# Lighting_Schematic_Design.net
KiCad netlist of a schematic drawn in EAGLE
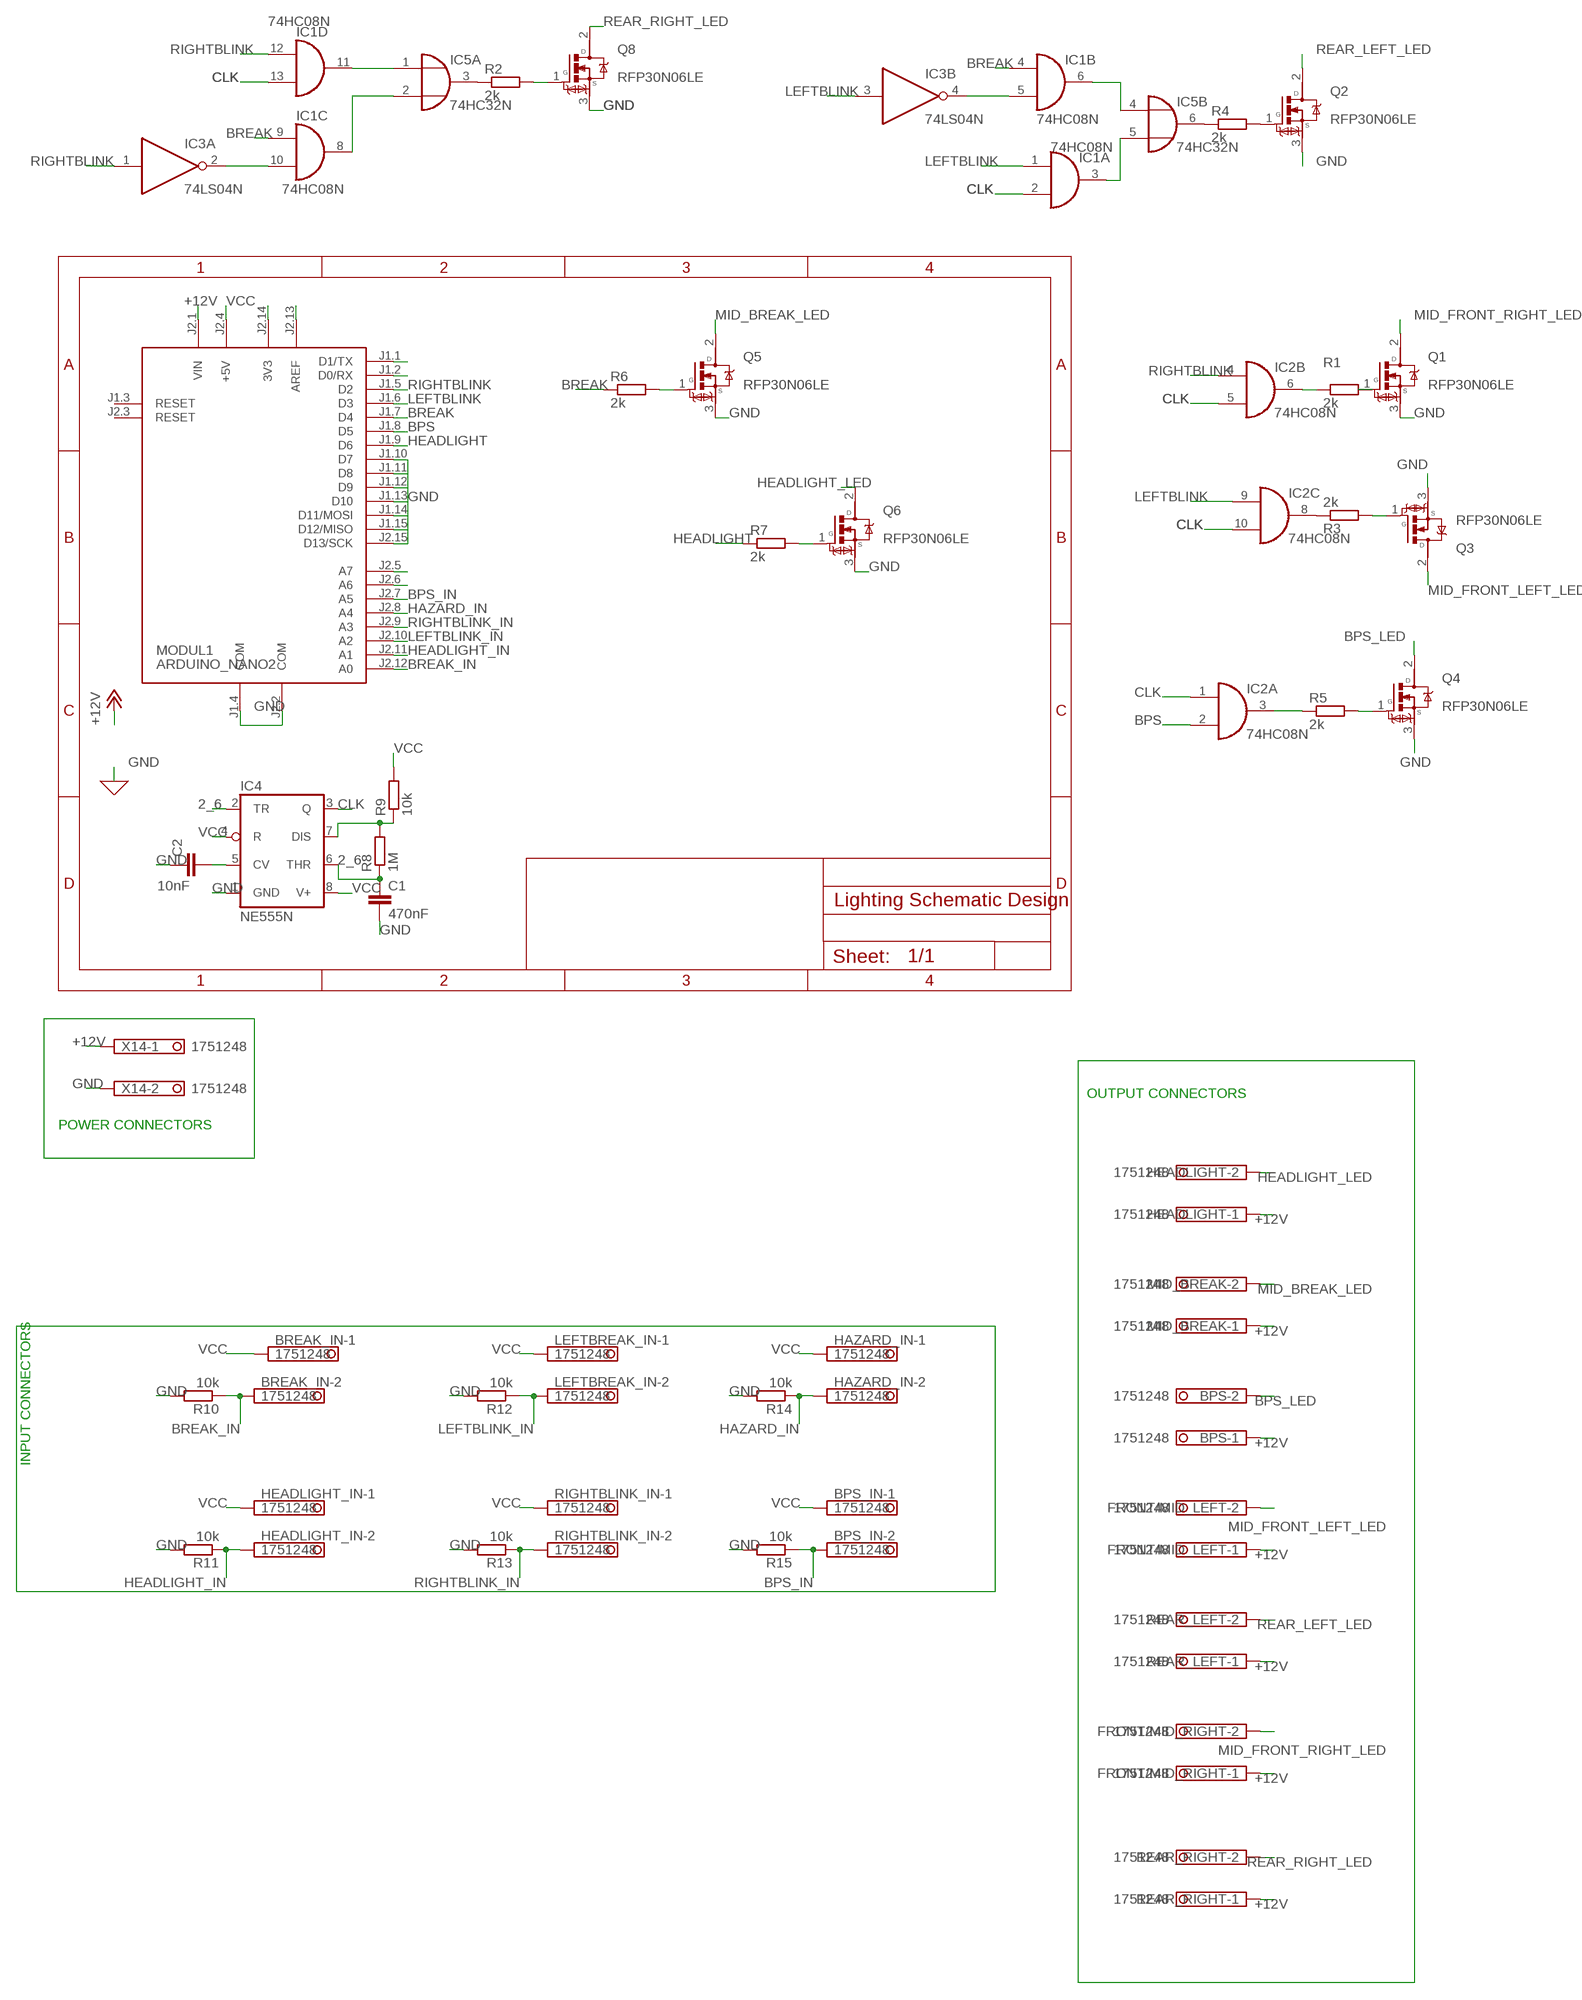
[diagram p0: schematic, sheet 1]

(export (version "E")
  (design (tool "Eeschema 10.0.6"))
  (components
    (comp (ref "BPS")
      (value "1751248")
      (footprint "eagle-import:1751248")
      (libsource (lib "eagle-import") (part "1751248"))
    )
    (comp (ref "BPS_IN")
      (value "1751248")
      (footprint "eagle-import:1751248")
      (libsource (lib "eagle-import") (part "1751248"))
    )
    (comp (ref "BREAK_IN")
      (value "1751248")
      (footprint "eagle-import:1751248")
      (libsource (lib "eagle-import") (part "1751248"))
    )
    (comp (ref "C1")
      (value "470nF")
      (footprint "eagle-import:C2.5-2")
      (libsource (lib "eagle-import") (part "C2.5/2"))
    )
    (comp (ref "C2")
      (value "10nF")
      (footprint "eagle-import:C2.5-2")
      (libsource (lib "eagle-import") (part "C2.5/2"))
    )
    (comp (ref "FRONT/MID_LEFT")
      (value "1751248")
      (footprint "eagle-import:1751248")
      (libsource (lib "eagle-import") (part "1751248"))
    )
    (comp (ref "FRONT/MID_RIGHT")
      (value "1751248")
      (footprint "eagle-import:1751248")
      (libsource (lib "eagle-import") (part "1751248"))
    )
    (comp (ref "HAZARD_IN")
      (value "1751248")
      (footprint "eagle-import:1751248")
      (libsource (lib "eagle-import") (part "1751248"))
    )
    (comp (ref "HEADLIGHT")
      (value "1751248")
      (footprint "eagle-import:1751248")
      (libsource (lib "eagle-import") (part "1751248"))
    )
    (comp (ref "HEADLIGHT_IN")
      (value "1751248")
      (footprint "eagle-import:1751248")
      (libsource (lib "eagle-import") (part "1751248"))
    )
    (comp (ref "IC1")
      (value "74HC08N")
      (footprint "eagle-import:DIL14")
      (libsource (lib "eagle-import") (part "7408NHC"))
    )
    (comp (ref "IC2")
      (value "74HC08N")
      (footprint "eagle-import:DIL14")
      (libsource (lib "eagle-import") (part "7408NHC"))
    )
    (comp (ref "IC3")
      (value "74LS04N")
      (footprint "eagle-import:DIL14")
      (libsource (lib "eagle-import") (part "7404NLS"))
    )
    (comp (ref "IC4")
      (value "NE555N")
      (footprint "eagle-import:DIL08")
      (libsource (lib "eagle-import") (part "555NNE"))
    )
    (comp (ref "IC5")
      (value "74HC32N")
      (footprint "eagle-import:DIL14")
      (libsource (lib "eagle-import") (part "7432NHC"))
    )
    (comp (ref "LEFTBREAK_IN")
      (value "1751248")
      (footprint "eagle-import:1751248")
      (libsource (lib "eagle-import") (part "1751248"))
    )
    (comp (ref "MID_BREAK")
      (value "1751248")
      (footprint "eagle-import:1751248")
      (libsource (lib "eagle-import") (part "1751248"))
    )
    (comp (ref "MODUL1")
      (value "ARDUINO_NANO2")
      (footprint "eagle-import:ARDUINO_NANO2")
      (libsource (lib "eagle-import") (part "ARDUINO_NANO2"))
    )
    (comp (ref "Q1")
      (value "RFP30N06LE")
      (footprint "eagle-import:TRANS_RFP30N06LE")
      (fields (field (name "MF") "ON Semiconductor"))
      (libsource (lib "eagle-import") (part "RFP30N06LE"))
    )
    (comp (ref "Q2")
      (value "RFP30N06LE")
      (footprint "eagle-import:TRANS_RFP30N06LE")
      (fields (field (name "MF") "ON Semiconductor"))
      (libsource (lib "eagle-import") (part "RFP30N06LE"))
    )
    (comp (ref "Q3")
      (value "RFP30N06LE")
      (footprint "eagle-import:TRANS_RFP30N06LE")
      (fields (field (name "MF") "ON Semiconductor"))
      (libsource (lib "eagle-import") (part "RFP30N06LE"))
    )
    (comp (ref "Q4")
      (value "RFP30N06LE")
      (footprint "eagle-import:TRANS_RFP30N06LE")
      (fields (field (name "MF") "ON Semiconductor"))
      (libsource (lib "eagle-import") (part "RFP30N06LE"))
    )
    (comp (ref "Q5")
      (value "RFP30N06LE")
      (footprint "eagle-import:TRANS_RFP30N06LE")
      (fields (field (name "MF") "ON Semiconductor"))
      (libsource (lib "eagle-import") (part "RFP30N06LE"))
    )
    (comp (ref "Q6")
      (value "RFP30N06LE")
      (footprint "eagle-import:TRANS_RFP30N06LE")
      (fields (field (name "MF") "ON Semiconductor"))
      (libsource (lib "eagle-import") (part "RFP30N06LE"))
    )
    (comp (ref "Q8")
      (value "RFP30N06LE")
      (footprint "eagle-import:TRANS_RFP30N06LE")
      (fields (field (name "MF") "ON Semiconductor"))
      (libsource (lib "eagle-import") (part "RFP30N06LE"))
    )
    (comp (ref "R1")
      (value "2k")
      (footprint "eagle-import:0204_5")
      (libsource (lib "eagle-import") (part "R-EU_0204/5"))
    )
    (comp (ref "R2")
      (value "2k")
      (footprint "eagle-import:0204_5")
      (libsource (lib "eagle-import") (part "R-EU_0204/5"))
    )
    (comp (ref "R3")
      (value "2k")
      (footprint "eagle-import:0204_5")
      (libsource (lib "eagle-import") (part "R-EU_0204/5"))
    )
    (comp (ref "R4")
      (value "2k")
      (footprint "eagle-import:0204_5")
      (libsource (lib "eagle-import") (part "R-EU_0204/5"))
    )
    (comp (ref "R5")
      (value "2k")
      (footprint "eagle-import:0204_5")
      (libsource (lib "eagle-import") (part "R-EU_0204/5"))
    )
    (comp (ref "R6")
      (value "2k")
      (footprint "eagle-import:0204_5")
      (libsource (lib "eagle-import") (part "R-EU_0204/5"))
    )
    (comp (ref "R7")
      (value "2k")
      (footprint "eagle-import:0204_5")
      (libsource (lib "eagle-import") (part "R-EU_0204/5"))
    )
    (comp (ref "R8")
      (value "1M")
      (footprint "eagle-import:0204_5")
      (libsource (lib "eagle-import") (part "R-EU_0204/5"))
    )
    (comp (ref "R9")
      (value "10k")
      (footprint "eagle-import:0204_5")
      (libsource (lib "eagle-import") (part "R-EU_0204/5"))
    )
    (comp (ref "R10")
      (value "10k")
      (footprint "eagle-import:0204_5")
      (libsource (lib "eagle-import") (part "R-EU_0204/5"))
    )
    (comp (ref "R11")
      (value "10k")
      (footprint "eagle-import:0204_5")
      (libsource (lib "eagle-import") (part "R-EU_0204/5"))
    )
    (comp (ref "R12")
      (value "10k")
      (footprint "eagle-import:0204_5")
      (libsource (lib "eagle-import") (part "R-EU_0204/5"))
    )
    (comp (ref "R13")
      (value "10k")
      (footprint "eagle-import:0204_5")
      (libsource (lib "eagle-import") (part "R-EU_0204/5"))
    )
    (comp (ref "R14")
      (value "10k")
      (footprint "eagle-import:0204_5")
      (libsource (lib "eagle-import") (part "R-EU_0204/5"))
    )
    (comp (ref "R15")
      (value "10k")
      (footprint "eagle-import:0204_5")
      (libsource (lib "eagle-import") (part "R-EU_0204/5"))
    )
    (comp (ref "REAR_LEFT")
      (value "1751248")
      (footprint "eagle-import:1751248")
      (libsource (lib "eagle-import") (part "1751248"))
    )
    (comp (ref "REAR_RIGHT")
      (value "1751248")
      (footprint "eagle-import:1751248")
      (libsource (lib "eagle-import") (part "1751248"))
    )
    (comp (ref "RIGHTBLINK_IN")
      (value "1751248")
      (footprint "eagle-import:1751248")
      (libsource (lib "eagle-import") (part "1751248"))
    )
    (comp (ref "X14")
      (value "1751248")
      (footprint "eagle-import:1751248")
      (libsource (lib "eagle-import") (part "1751248"))
    )
  )
  (nets
    (net (code "1") (name "+12V") (class "Default")
      (node (ref "BPS") (pin "1") (pinfunction "K_1") (pintype "passive"))
      (node (ref "FRONT/MID_LEFT") (pin "1") (pinfunction "K_1") (pintype "passive"))
      (node (ref "FRONT/MID_RIGHT") (pin "1") (pinfunction "K_1") (pintype "passive"))
      (node (ref "HEADLIGHT") (pin "1") (pinfunction "K_1") (pintype "passive"))
      (node (ref "MID_BREAK") (pin "1") (pinfunction "K_1") (pintype "passive"))
      (node (ref "MODUL1") (pin "J2.1") (pinfunction "VIN_J2.1") (pintype "power_in"))
      (node (ref "REAR_LEFT") (pin "1") (pinfunction "K_1") (pintype "passive"))
      (node (ref "REAR_RIGHT") (pin "1") (pinfunction "K_1") (pintype "passive"))
      (node (ref "X14") (pin "1") (pinfunction "K_1") (pintype "passive"))
    )
    (net (code "2") (name "/2_6") (class "Default")
      (node (ref "C1") (pin "1") (pinfunction "1_1") (pintype "passive"))
      (node (ref "IC4") (pin "2") (pinfunction "TR_2") (pintype "input"))
      (node (ref "IC4") (pin "6") (pinfunction "THR_6") (pintype "input"))
      (node (ref "R8") (pin "1") (pinfunction "1_1") (pintype "passive"))
    )
    (net (code "3") (name "/BPS") (class "Default")
      (node (ref "IC2") (pin "2") (pinfunction "I1_2") (pintype "input"))
      (node (ref "MODUL1") (pin "J1.8") (pinfunction "D5_J1.8") (pintype "bidirectional"))
    )
    (net (code "4") (name "/BPS_IN") (class "Default")
      (node (ref "BPS_IN") (pin "2") (pinfunction "K_2") (pintype "passive"))
      (node (ref "MODUL1") (pin "J2.7") (pinfunction "A5_J2.7") (pintype "bidirectional"))
      (node (ref "R15") (pin "1") (pinfunction "1_1") (pintype "passive"))
    )
    (net (code "5") (name "/BPS_LED") (class "Default")
      (node (ref "BPS") (pin "2") (pinfunction "K_2") (pintype "passive"))
      (node (ref "Q4") (pin "2") (pinfunction "D_2") (pintype "power_in"))
    )
    (net (code "6") (name "/BREAK") (class "Default")
      (node (ref "IC1") (pin "4") (pinfunction "I0_4") (pintype "input"))
      (node (ref "IC1") (pin "9") (pinfunction "I0_9") (pintype "input"))
      (node (ref "MODUL1") (pin "J1.7") (pinfunction "D4_J1.7") (pintype "bidirectional"))
      (node (ref "R6") (pin "1") (pinfunction "1_1") (pintype "passive"))
    )
    (net (code "7") (name "/BREAK_IN") (class "Default")
      (node (ref "BREAK_IN") (pin "2") (pinfunction "K_2") (pintype "passive"))
      (node (ref "MODUL1") (pin "J2.12") (pinfunction "A0_J2.12") (pintype "bidirectional"))
      (node (ref "R10") (pin "1") (pinfunction "1_1") (pintype "passive"))
    )
    (net (code "8") (name "/CLK") (class "Default")
      (node (ref "IC1") (pin "13") (pinfunction "I1_13") (pintype "input"))
      (node (ref "IC1") (pin "2") (pinfunction "I1_2") (pintype "input"))
      (node (ref "IC2") (pin "1") (pinfunction "I0_1") (pintype "input"))
      (node (ref "IC2") (pin "10") (pinfunction "I1_10") (pintype "input"))
      (node (ref "IC2") (pin "5") (pinfunction "I1_5") (pintype "input"))
      (node (ref "IC4") (pin "3") (pinfunction "Q_3") (pintype "output"))
    )
    (net (code "9") (name "/HAZARD_IN") (class "Default")
      (node (ref "HAZARD_IN") (pin "2") (pinfunction "K_2") (pintype "passive"))
      (node (ref "MODUL1") (pin "J2.8") (pinfunction "A4_J2.8") (pintype "bidirectional"))
      (node (ref "R14") (pin "1") (pinfunction "1_1") (pintype "passive"))
    )
    (net (code "10") (name "/HEADLIGHT") (class "Default")
      (node (ref "MODUL1") (pin "J1.9") (pinfunction "D6_J1.9") (pintype "bidirectional"))
      (node (ref "R7") (pin "1") (pinfunction "1_1") (pintype "passive"))
    )
    (net (code "11") (name "/HEADLIGHT_IN") (class "Default")
      (node (ref "HEADLIGHT_IN") (pin "2") (pinfunction "K_2") (pintype "passive"))
      (node (ref "MODUL1") (pin "J2.11") (pinfunction "A1_J2.11") (pintype "bidirectional"))
      (node (ref "R11") (pin "1") (pinfunction "1_1") (pintype "passive"))
    )
    (net (code "12") (name "/HEADLIGHT_LED") (class "Default")
      (node (ref "HEADLIGHT") (pin "2") (pinfunction "K_2") (pintype "passive"))
      (node (ref "Q6") (pin "2") (pinfunction "D_2") (pintype "power_in"))
    )
    (net (code "13") (name "/LEFTBLINK") (class "Default")
      (node (ref "IC1") (pin "1") (pinfunction "I0_1") (pintype "input"))
      (node (ref "IC2") (pin "9") (pinfunction "I0_9") (pintype "input"))
      (node (ref "IC3") (pin "3") (pinfunction "I_3") (pintype "input"))
      (node (ref "MODUL1") (pin "J1.6") (pinfunction "D3_J1.6") (pintype "bidirectional"))
    )
    (net (code "14") (name "/LEFTBLINK_IN") (class "Default")
      (node (ref "LEFTBREAK_IN") (pin "2") (pinfunction "K_2") (pintype "passive"))
      (node (ref "MODUL1") (pin "J2.10") (pinfunction "A2_J2.10") (pintype "bidirectional"))
      (node (ref "R12") (pin "1") (pinfunction "1_1") (pintype "passive"))
    )
    (net (code "15") (name "/MID_BREAK_LED") (class "Default")
      (node (ref "MID_BREAK") (pin "2") (pinfunction "K_2") (pintype "passive"))
      (node (ref "Q5") (pin "2") (pinfunction "D_2") (pintype "power_in"))
    )
    (net (code "16") (name "/MID_FRONT_LEFT_LED") (class "Default")
      (node (ref "FRONT/MID_LEFT") (pin "2") (pinfunction "K_2") (pintype "passive"))
      (node (ref "Q3") (pin "2") (pinfunction "D_2") (pintype "power_in"))
    )
    (net (code "17") (name "/MID_FRONT_RIGHT_LED") (class "Default")
      (node (ref "FRONT/MID_RIGHT") (pin "2") (pinfunction "K_2") (pintype "passive"))
      (node (ref "Q1") (pin "2") (pinfunction "D_2") (pintype "power_in"))
    )
    (net (code "18") (name "/REAR_LEFT_LED") (class "Default")
      (node (ref "Q2") (pin "2") (pinfunction "D_2") (pintype "power_in"))
      (node (ref "REAR_LEFT") (pin "2") (pinfunction "K_2") (pintype "passive"))
    )
    (net (code "19") (name "/REAR_RIGHT_LED") (class "Default")
      (node (ref "Q8") (pin "2") (pinfunction "D_2") (pintype "power_in"))
      (node (ref "REAR_RIGHT") (pin "2") (pinfunction "K_2") (pintype "passive"))
    )
    (net (code "20") (name "/RIGHTBLINK") (class "Default")
      (node (ref "IC1") (pin "12") (pinfunction "I0_12") (pintype "input"))
      (node (ref "IC2") (pin "4") (pinfunction "I0_4") (pintype "input"))
      (node (ref "IC3") (pin "1") (pinfunction "I_1") (pintype "input"))
      (node (ref "MODUL1") (pin "J1.5") (pinfunction "D2_J1.5") (pintype "bidirectional"))
    )
    (net (code "21") (name "/RIGHTBLINK_IN") (class "Default")
      (node (ref "MODUL1") (pin "J2.9") (pinfunction "A3_J2.9") (pintype "bidirectional"))
      (node (ref "R13") (pin "1") (pinfunction "1_1") (pintype "passive"))
      (node (ref "RIGHTBLINK_IN") (pin "2") (pinfunction "K_2") (pintype "passive"))
    )
    (net (code "22") (name "/VCC") (class "Default")
      (node (ref "BPS_IN") (pin "1") (pinfunction "K_1") (pintype "passive"))
      (node (ref "BREAK_IN") (pin "1") (pinfunction "K_1") (pintype "passive"))
      (node (ref "HAZARD_IN") (pin "1") (pinfunction "K_1") (pintype "passive"))
      (node (ref "HEADLIGHT_IN") (pin "1") (pinfunction "K_1") (pintype "passive"))
      (node (ref "IC4") (pin "4") (pinfunction "R_4") (pintype "input"))
      (node (ref "IC4") (pin "8") (pinfunction "V+_8") (pintype "power_in"))
      (node (ref "LEFTBREAK_IN") (pin "1") (pinfunction "K_1") (pintype "passive"))
      (node (ref "MODUL1") (pin "J2.4") (pinfunction "+5V_J2.4") (pintype "power_in"))
      (node (ref "R9") (pin "2") (pinfunction "2_2") (pintype "passive"))
      (node (ref "RIGHTBLINK_IN") (pin "1") (pinfunction "K_1") (pintype "passive"))
    )
    (net (code "23") (name "GND") (class "Default")
      (node (ref "C1") (pin "2") (pinfunction "2_2") (pintype "passive"))
      (node (ref "C2") (pin "1") (pinfunction "1_1") (pintype "passive"))
      (node (ref "IC4") (pin "1") (pinfunction "GND_1") (pintype "power_in"))
      (node (ref "MODUL1") (pin "J1.10") (pinfunction "D7_J1.10") (pintype "bidirectional"))
      (node (ref "MODUL1") (pin "J1.4") (pinfunction "COM_J1.4") (pintype "power_in"))
      (node (ref "MODUL1") (pin "J2.15") (pinfunction "D13/SCK_J2.15") (pintype "bidirectional"))
      (node (ref "MODUL1") (pin "J2.2") (pinfunction "COM_J2.2") (pintype "power_in"))
      (node (ref "Q1") (pin "3") (pinfunction "S_3") (pintype "power_in"))
      (node (ref "Q2") (pin "3") (pinfunction "S_3") (pintype "power_in"))
      (node (ref "Q3") (pin "3") (pinfunction "S_3") (pintype "power_in"))
      (node (ref "Q4") (pin "3") (pinfunction "S_3") (pintype "power_in"))
      (node (ref "Q5") (pin "3") (pinfunction "S_3") (pintype "power_in"))
      (node (ref "Q6") (pin "3") (pinfunction "S_3") (pintype "power_in"))
      (node (ref "Q8") (pin "3") (pinfunction "S_3") (pintype "power_in"))
      (node (ref "R10") (pin "2") (pinfunction "2_2") (pintype "passive"))
      (node (ref "R11") (pin "2") (pinfunction "2_2") (pintype "passive"))
      (node (ref "R12") (pin "2") (pinfunction "2_2") (pintype "passive"))
      (node (ref "R13") (pin "2") (pinfunction "2_2") (pintype "passive"))
      (node (ref "R14") (pin "2") (pinfunction "2_2") (pintype "passive"))
      (node (ref "R15") (pin "2") (pinfunction "2_2") (pintype "passive"))
      (node (ref "X14") (pin "2") (pinfunction "K_2") (pintype "passive"))
    )
    (net (code "24") (name "Net-(IC1A-O)") (class "Default")
      (node (ref "IC1") (pin "3") (pinfunction "O_3") (pintype "output"))
      (node (ref "IC5") (pin "5") (pinfunction "I1_5") (pintype "input"))
    )
    (net (code "25") (name "Net-(IC1B-I1)") (class "Default")
      (node (ref "IC1") (pin "5") (pinfunction "I1_5") (pintype "input"))
      (node (ref "IC3") (pin "4") (pinfunction "O_4") (pintype "output"))
    )
    (net (code "26") (name "Net-(IC1B-O)") (class "Default")
      (node (ref "IC1") (pin "6") (pinfunction "O_6") (pintype "output"))
      (node (ref "IC5") (pin "4") (pinfunction "I0_4") (pintype "input"))
    )
    (net (code "27") (name "Net-(IC1C-I1)") (class "Default")
      (node (ref "IC1") (pin "10") (pinfunction "I1_10") (pintype "input"))
      (node (ref "IC3") (pin "2") (pinfunction "O_2") (pintype "output"))
    )
    (net (code "28") (name "Net-(IC1C-O)") (class "Default")
      (node (ref "IC1") (pin "8") (pinfunction "O_8") (pintype "output"))
      (node (ref "IC5") (pin "2") (pinfunction "I1_2") (pintype "input"))
    )
    (net (code "29") (name "Net-(IC1D-O)") (class "Default")
      (node (ref "IC1") (pin "11") (pinfunction "O_11") (pintype "output"))
      (node (ref "IC5") (pin "1") (pinfunction "I0_1") (pintype "input"))
    )
    (net (code "30") (name "Net-(IC2A-O)") (class "Default")
      (node (ref "IC2") (pin "3") (pinfunction "O_3") (pintype "output"))
      (node (ref "R5") (pin "1") (pinfunction "1_1") (pintype "passive"))
    )
    (net (code "31") (name "Net-(IC2B-O)") (class "Default")
      (node (ref "IC2") (pin "6") (pinfunction "O_6") (pintype "output"))
      (node (ref "R1") (pin "1") (pinfunction "1_1") (pintype "passive"))
    )
    (net (code "32") (name "Net-(IC2C-O)") (class "Default")
      (node (ref "IC2") (pin "8") (pinfunction "O_8") (pintype "output"))
      (node (ref "R3") (pin "1") (pinfunction "1_1") (pintype "passive"))
    )
    (net (code "33") (name "Net-(IC4-CV)") (class "Default")
      (node (ref "C2") (pin "2") (pinfunction "2_2") (pintype "passive"))
      (node (ref "IC4") (pin "5") (pinfunction "CV_5") (pintype "input"))
    )
    (net (code "34") (name "Net-(IC4-DIS)") (class "Default")
      (node (ref "IC4") (pin "7") (pinfunction "DIS_7") (pintype "input"))
      (node (ref "R8") (pin "2") (pinfunction "2_2") (pintype "passive"))
      (node (ref "R9") (pin "1") (pinfunction "1_1") (pintype "passive"))
    )
    (net (code "35") (name "Net-(IC5A-O)") (class "Default")
      (node (ref "IC5") (pin "3") (pinfunction "O_3") (pintype "output"))
      (node (ref "R2") (pin "1") (pinfunction "1_1") (pintype "passive"))
    )
    (net (code "36") (name "Net-(IC5B-O)") (class "Default")
      (node (ref "IC5") (pin "6") (pinfunction "O_6") (pintype "output"))
      (node (ref "R4") (pin "1") (pinfunction "1_1") (pintype "passive"))
    )
    (net (code "37") (name "Net-(Q1-G)") (class "Default")
      (node (ref "Q1") (pin "1") (pinfunction "G_1") (pintype "input"))
      (node (ref "R1") (pin "2") (pinfunction "2_2") (pintype "passive"))
    )
    (net (code "38") (name "Net-(Q2-G)") (class "Default")
      (node (ref "Q2") (pin "1") (pinfunction "G_1") (pintype "input"))
      (node (ref "R4") (pin "2") (pinfunction "2_2") (pintype "passive"))
    )
    (net (code "39") (name "Net-(Q3-G)") (class "Default")
      (node (ref "Q3") (pin "1") (pinfunction "G_1") (pintype "input"))
      (node (ref "R3") (pin "2") (pinfunction "2_2") (pintype "passive"))
    )
    (net (code "40") (name "Net-(Q4-G)") (class "Default")
      (node (ref "Q4") (pin "1") (pinfunction "G_1") (pintype "input"))
      (node (ref "R5") (pin "2") (pinfunction "2_2") (pintype "passive"))
    )
    (net (code "41") (name "Net-(Q5-G)") (class "Default")
      (node (ref "Q5") (pin "1") (pinfunction "G_1") (pintype "input"))
      (node (ref "R6") (pin "2") (pinfunction "2_2") (pintype "passive"))
    )
    (net (code "42") (name "Net-(Q6-G)") (class "Default")
      (node (ref "Q6") (pin "1") (pinfunction "G_1") (pintype "input"))
      (node (ref "R7") (pin "2") (pinfunction "2_2") (pintype "passive"))
    )
    (net (code "43") (name "Net-(Q8-G)") (class "Default")
      (node (ref "Q8") (pin "1") (pinfunction "G_1") (pintype "input"))
      (node (ref "R2") (pin "2") (pinfunction "2_2") (pintype "passive"))
    )
    (net (code "44") (name "unconnected-(MODUL1-3V3-PadJ2.14)") (class "Default")
      (node (ref "MODUL1") (pin "J2.14") (pinfunction "3V3_J2.14") (pintype "power_in"))
    )
    (net (code "45") (name "unconnected-(MODUL1-A6-PadJ2.6)") (class "Default")
      (node (ref "MODUL1") (pin "J2.6") (pinfunction "A6_J2.6") (pintype "bidirectional"))
    )
    (net (code "46") (name "unconnected-(MODUL1-A7-PadJ2.5)") (class "Default")
      (node (ref "MODUL1") (pin "J2.5") (pinfunction "A7_J2.5") (pintype "bidirectional"))
    )
    (net (code "47") (name "unconnected-(MODUL1-AREF-PadJ2.13)") (class "Default")
      (node (ref "MODUL1") (pin "J2.13") (pinfunction "AREF_J2.13") (pintype "power_in"))
    )
    (net (code "48") (name "unconnected-(MODUL1-D0{slash}RX-PadJ1.2)") (class "Default")
      (node (ref "MODUL1") (pin "J1.2") (pinfunction "D0/RX_J1.2") (pintype "bidirectional"))
    )
    (net (code "49") (name "unconnected-(MODUL1-D1{slash}TX-PadJ1.1)") (class "Default")
      (node (ref "MODUL1") (pin "J1.1") (pinfunction "D1/TX_J1.1") (pintype "bidirectional"))
    )
    (net (code "50") (name "unconnected-(MODUL1-D8-PadJ1.11)") (class "Default")
      (node (ref "MODUL1") (pin "J1.11") (pinfunction "D8_J1.11") (pintype "bidirectional"))
    )
    (net (code "51") (name "unconnected-(MODUL1-D9-PadJ1.12)") (class "Default")
      (node (ref "MODUL1") (pin "J1.12") (pinfunction "D9_J1.12") (pintype "bidirectional"))
    )
    (net (code "52") (name "unconnected-(MODUL1-D10-PadJ1.13)") (class "Default")
      (node (ref "MODUL1") (pin "J1.13") (pinfunction "D10_J1.13") (pintype "bidirectional"))
    )
    (net (code "53") (name "unconnected-(MODUL1-D11{slash}MOSI-PadJ1.14)") (class "Default")
      (node (ref "MODUL1") (pin "J1.14") (pinfunction "D11/MOSI_J1.14") (pintype "bidirectional"))
    )
    (net (code "54") (name "unconnected-(MODUL1-D12{slash}MISO-PadJ1.15)") (class "Default")
      (node (ref "MODUL1") (pin "J1.15") (pinfunction "D12/MISO_J1.15") (pintype "bidirectional"))
    )
    (net (code "55") (name "unconnected-(MODUL1-RESET-PadJ1.3)") (class "Default")
      (node (ref "MODUL1") (pin "J1.3") (pinfunction "RESET_J1.3") (pintype "bidirectional"))
    )
    (net (code "56") (name "unconnected-(MODUL1-RESET-PadJ2.3)") (class "Default")
      (node (ref "MODUL1") (pin "J2.3") (pinfunction "RESET_J2.3") (pintype "bidirectional"))
    )
  )
)
